# main.net
KiCad netlist of a schematic drawn in Altium Designer
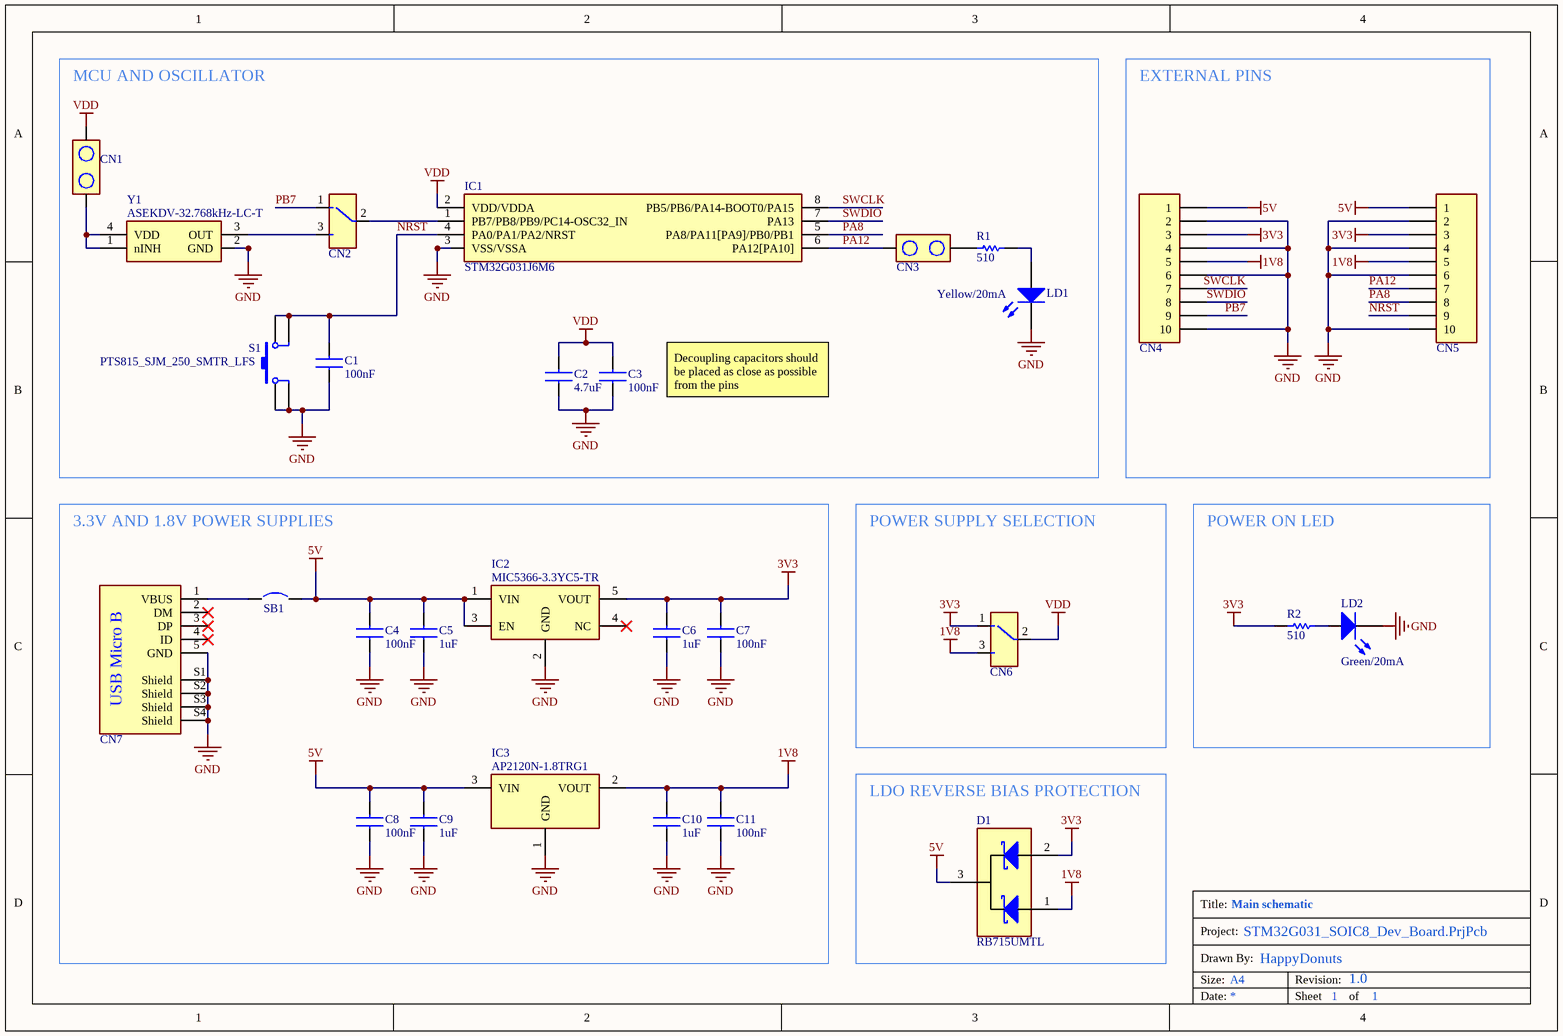
[diagram p0: main.SchDoc]

(export (version "E")
  (design (tool "Eeschema 10.0.6"))
  (components
    (comp (ref "C1")
      (value "100nF")
      (footprint "STM32G031_SOIC8_Dev_Board:CAPC2012X94N")
      (description "Capacitor")
      (fields
        (field (name "MANUFACTURER_PART_NUMBER") "C0805C104K5RAC7411")
        (field (name "MOUSER PART NUMBER") "80-C0805C104K5RACLR")
      )
      (libsource (lib "STM32G031_SOIC8_Dev_Board") (part "C0805C104K5RAC7411"))
    )
    (comp (ref "C2")
      (value "4.7uF")
      (footprint "STM32G031_SOIC8_Dev_Board:CAPC2012X135N")
      (description "Capacitor")
      (fields
        (field (name "MANUFACTURER_PART_NUMBER") "CL21A475KPFNNNE")
        (field (name "MOUSER PART NUMBER") "187-CL21A475KPFNNNE")
      )
      (libsource (lib "STM32G031_SOIC8_Dev_Board") (part "CL21A475KPFNNNE"))
    )
    (comp (ref "C3")
      (value "100nF")
      (footprint "STM32G031_SOIC8_Dev_Board:CAPC2012X94N")
      (description "Capacitor")
      (fields
        (field (name "MANUFACTURER_PART_NUMBER") "C0805C104K5RAC7411")
        (field (name "MOUSER PART NUMBER") "80-C0805C104K5RACLR")
      )
      (libsource (lib "STM32G031_SOIC8_Dev_Board") (part "C0805C104K5RAC7411"))
    )
    (comp (ref "C4")
      (value "100nF")
      (footprint "STM32G031_SOIC8_Dev_Board:CAPC2012X94N")
      (description "Capacitor")
      (fields
        (field (name "MANUFACTURER_PART_NUMBER") "C0805C104K5RAC7411")
        (field (name "MOUSER PART NUMBER") "80-C0805C104K5RACLR")
      )
      (libsource (lib "STM32G031_SOIC8_Dev_Board") (part "C0805C104K5RAC7411"))
    )
    (comp (ref "C5")
      (value "1uF")
      (footprint "STM32G031_SOIC8_Dev_Board:CAPC2012X135N")
      (description "Capacitor")
      (fields
        (field (name "MANUFACTURER_PART_NUMBER") "885012107015")
        (field (name "MOUSER PART NUMBER") "710-885012107015")
      )
      (libsource (lib "STM32G031_SOIC8_Dev_Board") (part "885012107015"))
    )
    (comp (ref "C6")
      (value "1uF")
      (footprint "STM32G031_SOIC8_Dev_Board:CAPC2012X135N")
      (description "Capacitor")
      (fields
        (field (name "MANUFACTURER_PART_NUMBER") "885012107015")
        (field (name "MOUSER PART NUMBER") "710-885012107015")
      )
      (libsource (lib "STM32G031_SOIC8_Dev_Board") (part "885012107015"))
    )
    (comp (ref "C7")
      (value "100nF")
      (footprint "STM32G031_SOIC8_Dev_Board:CAPC2012X94N")
      (description "Capacitor")
      (fields
        (field (name "MANUFACTURER_PART_NUMBER") "C0805C104K5RAC7411")
        (field (name "MOUSER PART NUMBER") "80-C0805C104K5RACLR")
      )
      (libsource (lib "STM32G031_SOIC8_Dev_Board") (part "C0805C104K5RAC7411"))
    )
    (comp (ref "C8")
      (value "100nF")
      (footprint "STM32G031_SOIC8_Dev_Board:CAPC2012X94N")
      (description "Capacitor")
      (fields
        (field (name "MANUFACTURER_PART_NUMBER") "C0805C104K5RAC7411")
        (field (name "MOUSER PART NUMBER") "80-C0805C104K5RACLR")
      )
      (libsource (lib "STM32G031_SOIC8_Dev_Board") (part "C0805C104K5RAC7411"))
    )
    (comp (ref "C9")
      (value "1uF")
      (footprint "STM32G031_SOIC8_Dev_Board:CAPC2012X135N")
      (description "Capacitor")
      (fields
        (field (name "MANUFACTURER_PART_NUMBER") "885012107015")
        (field (name "MOUSER PART NUMBER") "710-885012107015")
      )
      (libsource (lib "STM32G031_SOIC8_Dev_Board") (part "885012107015"))
    )
    (comp (ref "C10")
      (value "1uF")
      (footprint "STM32G031_SOIC8_Dev_Board:CAPC2012X135N")
      (description "Capacitor")
      (fields
        (field (name "MANUFACTURER_PART_NUMBER") "885012107015")
        (field (name "MOUSER PART NUMBER") "710-885012107015")
      )
      (libsource (lib "STM32G031_SOIC8_Dev_Board") (part "885012107015"))
    )
    (comp (ref "C11")
      (value "100nF")
      (footprint "STM32G031_SOIC8_Dev_Board:CAPC2012X94N")
      (description "Capacitor")
      (fields
        (field (name "MANUFACTURER_PART_NUMBER") "C0805C104K5RAC7411")
        (field (name "MOUSER PART NUMBER") "80-C0805C104K5RACLR")
      )
      (libsource (lib "STM32G031_SOIC8_Dev_Board") (part "C0805C104K5RAC7411"))
    )
    (comp (ref "CN1")
      (value "CN_2PIN")
      (footprint "STM32G031_SOIC8_Dev_Board:CN_2PIN")
      (description "Connector")
      (libsource (lib "") (part "CN_2PIN_1"))
    )
    (comp (ref "CN2")
      (value "CN_3PIN")
      (footprint "STM32G031_SOIC8_Dev_Board:CN_3PIN")
      (description "Connector")
      (libsource (lib "STM32G031_SOIC8_Dev_Board") (part "CN_3PIN"))
    )
    (comp (ref "CN3")
      (value "CN_2PIN")
      (footprint "STM32G031_SOIC8_Dev_Board:CN_2PIN")
      (description "Connector")
      (libsource (lib "STM32G031_SOIC8_Dev_Board") (part "CN_2PIN"))
    )
    (comp (ref "CN4")
      (value "CN_10PIN")
      (footprint "STM32G031_SOIC8_Dev_Board:CN_10PIN")
      (description "Connector")
      (libsource (lib "") (part "CN_10PIN_1"))
    )
    (comp (ref "CN5")
      (value "CN_10PIN")
      (footprint "STM32G031_SOIC8_Dev_Board:CN_10PIN")
      (description "Connector")
      (libsource (lib "STM32G031_SOIC8_Dev_Board") (part "CN_10PIN"))
    )
    (comp (ref "CN6")
      (value "CN_3PIN")
      (footprint "STM32G031_SOIC8_Dev_Board:CN_3PIN")
      (description "Connector")
      (libsource (lib "STM32G031_SOIC8_Dev_Board") (part "CN_3PIN"))
    )
    (comp (ref "CN7")
      (value "USB_B_AE")
      (footprint "STM32G031_SOIC8_Dev_Board:USB_B_AE")
      (description "USB connector")
      (libsource (lib "STM32G031_SOIC8_Dev_Board") (part "USB_B_AE"))
    )
    (comp (ref "D1")
      (value "RB715UMTL")
      (footprint "STM32L031_TSSOP20_Dev_Board:DAN217UMTL")
      (description "Schottky Diode")
      (fields (field (name "MOUSER PART NUMBER") "755-RB715UMTL"))
      (libsource (lib "STM32G031_SOIC8_Dev_Board") (part "RB715UMTL"))
    )
    (comp (ref "IC1")
      (value "STM32G031J6M6")
      (footprint "STM32G031_SOIC8_Dev_Board:SOIC127P600X175-8N")
      (description "Integrated Circuit")
      (fields (field (name "MOUSER PART NUMBER") "511-STM32G031J6M6"))
      (libsource (lib "STM32G031_SOIC8_Dev_Board") (part "STM32G031J6M6"))
    )
    (comp (ref "IC2")
      (value "MIC5366-3.3YC5-TR")
      (footprint "STM32G031_SOIC8_Dev_Board:SOT65P210X110-5N")
      (description "LDO")
      (fields
        (field (name "MOUSER PART NUMBER") "998-MIC5366-3.3YC5TR")
        (field (name "ARROW PART NUMBER") "MIC5365-3.3YC5-TR")
      )
      (libsource (lib "STM32G031_SOIC8_Dev_Board") (part "MIC5366-3.3YC5-TR"))
    )
    (comp (ref "IC3")
      (value "AP2120N-1.8TRG1")
      (footprint "STM32G031_SOIC8_Dev_Board:SOT95P230X110-3N")
      (description "LDO")
      (fields (field (name "MOUSER PART NUMBER") "621-AP2120N-1.8TRG1"))
      (libsource (lib "STM32G031_SOIC8_Dev_Board") (part "AP2120N-1.8TRG1"))
    )
    (comp (ref "LD1")
      (value "Yellow/20mA")
      (footprint "STM32G031_SOIC8_Dev_Board:LEDC2012X85N_Y")
      (description "LED")
      (fields
        (field (name "MANUFACTURER_PART_NUMBER") "LTST-C171KSKT")
        (field (name "MOUSER PART NUMBER") "859-LTST-C171KSKT")
      )
      (libsource (lib "STM32G031_SOIC8_Dev_Board") (part "LTST-C171KSKT"))
    )
    (comp (ref "LD2")
      (value "Green/20mA")
      (footprint "STM32G031_SOIC8_Dev_Board:LEDC2012X85N_G")
      (description "LED")
      (fields
        (field (name "MANUFACTURER_PART_NUMBER") "LTST-C171KGKT")
        (field (name "MOUSER PART NUMBER") "859-LTST-C171KGKT")
      )
      (libsource (lib "STM32G031_SOIC8_Dev_Board") (part "LTST-C171KGKT"))
    )
    (comp (ref "R1")
      (value "510")
      (footprint "STM32G031_SOIC8_Dev_Board:RESC2012X60N")
      (description "Resistor")
      (fields
        (field (name "MANUFACTURER_PART_NUMBER") "RC0805FR-07510RL")
        (field (name "MOUSER PART NUMBER") "603-RC0805FR-07510RL")
      )
      (libsource (lib "STM32G031_SOIC8_Dev_Board") (part "RC0805FR-07510RL"))
    )
    (comp (ref "R2")
      (value "510")
      (footprint "STM32G031_SOIC8_Dev_Board:RESC2012X60N")
      (description "Resistor")
      (fields
        (field (name "MANUFACTURER_PART_NUMBER") "RC0805FR-07510RL")
        (field (name "MOUSER PART NUMBER") "603-RC0805FR-07510RL")
      )
      (libsource (lib "STM32G031_SOIC8_Dev_Board") (part "RC0805FR-07510RL"))
    )
    (comp (ref "S1")
      (value "PTS815_SJM_250_SMTR_LFS")
      (footprint "STM32G031_SOIC8_Dev_Board:PTS815SJM250SMTRLFS")
      (description "Switch")
      (fields
        (field (name "MANUFACTURER_PART_NUMBER") "PTS815 SJM 250 SMTR LFS")
        (field (name "MOUSER PART NUMBER") "611-PTS815SJM250SMTR")
      )
      (libsource (lib "STM32G031_SOIC8_Dev_Board") (part "PTS815_SJM_250_SMTR_LFS"))
    )
    (comp (ref "SB1")
      (value "RC0805FR-070RL")
      (footprint "STM32G031_SOIC8_Dev_Board:RESC2012X60N")
      (description "Jumper (0 ohm)")
      (fields (field (name "MOUSER PART NUMBER") "603-RC0805FR-070RL"))
      (libsource (lib "STM32G031_SOIC8_Dev_Board") (part "RC0805FR-070RL"))
    )
    (comp (ref "Y1")
      (value "ASEKDV-32.768kHz-LC-T")
      (footprint "STM32G031_SOIC8_Dev_Board:ASEKDV-32.768kHz-LC-T")
      (description "Crystal or Oscillator")
      (fields (field (name "MOUSER PART NUMBER") "815-ASEKDV32768KHLCT"))
      (libsource (lib "STM32G031_SOIC8_Dev_Board") (part "ASEKDV-32.768kHz-LC-T"))
    )
  )
  (nets
    (net (code "1") (name "/NRST") (class "Default")
      (node (ref "C1") (pin "2") (pinfunction "2_2") (pintype "passive"))
      (node (ref "CN5") (pin "9") (pinfunction "9_9") (pintype "passive"))
      (node (ref "IC1") (pin "4") (pinfunction "PA0/PA1/PA2/NRST_4") (pintype "passive"))
      (node (ref "S1") (pin "3") (pinfunction "3_3") (pintype "passive"))
      (node (ref "S1") (pin "4") (pinfunction "4_4") (pintype "passive"))
    )
    (net (code "2") (name "/PA8") (class "Default")
      (node (ref "CN5") (pin "8") (pinfunction "8_8") (pintype "passive"))
      (node (ref "IC1") (pin "5") (pinfunction "PA8/PA11[PA9]/PB0/PB1_5") (pintype "passive"))
    )
    (net (code "3") (name "/PA12") (class "Default")
      (node (ref "CN3") (pin "1") (pinfunction "1_1") (pintype "passive"))
      (node (ref "CN5") (pin "7") (pinfunction "7_7") (pintype "passive"))
      (node (ref "IC1") (pin "6") (pinfunction "PA12[PA10]_6") (pintype "passive"))
    )
    (net (code "4") (name "/PB7") (class "Default")
      (node (ref "CN2") (pin "1") (pinfunction "1_1") (pintype "passive"))
      (node (ref "CN4") (pin "9") (pinfunction "9_9") (pintype "passive"))
    )
    (net (code "5") (name "/SWCLK") (class "Default")
      (node (ref "CN4") (pin "7") (pinfunction "7_7") (pintype "passive"))
      (node (ref "IC1") (pin "8") (pinfunction "PB5/PB6/PA14-BOOT0/PA15_8") (pintype "passive"))
    )
    (net (code "6") (name "/SWDIO") (class "Default")
      (node (ref "CN4") (pin "8") (pinfunction "8_8") (pintype "passive"))
      (node (ref "IC1") (pin "7") (pinfunction "PA13_7") (pintype "passive"))
    )
    (net (code "7") (name "1V8") (class "Default")
      (node (ref "C10") (pin "2") (pinfunction "2_2") (pintype "passive"))
      (node (ref "C11") (pin "2") (pinfunction "2_2") (pintype "passive"))
      (node (ref "CN4") (pin "5") (pinfunction "5_5") (pintype "passive"))
      (node (ref "CN5") (pin "5") (pinfunction "5_5") (pintype "passive"))
      (node (ref "CN6") (pin "3") (pinfunction "3_3") (pintype "passive"))
      (node (ref "D1") (pin "1") (pinfunction "K_1_1") (pintype "passive"))
      (node (ref "IC3") (pin "2") (pinfunction "VOUT_2") (pintype "passive"))
    )
    (net (code "8") (name "3V3") (class "Default")
      (node (ref "C6") (pin "2") (pinfunction "2_2") (pintype "passive"))
      (node (ref "C7") (pin "2") (pinfunction "2_2") (pintype "passive"))
      (node (ref "CN4") (pin "3") (pinfunction "3_3") (pintype "passive"))
      (node (ref "CN5") (pin "3") (pinfunction "3_3") (pintype "passive"))
      (node (ref "CN6") (pin "1") (pinfunction "1_1") (pintype "passive"))
      (node (ref "D1") (pin "2") (pinfunction "K_2_2") (pintype "passive"))
      (node (ref "IC2") (pin "5") (pinfunction "VOUT_5") (pintype "passive"))
      (node (ref "R2") (pin "1") (pinfunction "1_1") (pintype "passive"))
    )
    (net (code "9") (name "5V") (class "Default")
      (node (ref "C4") (pin "2") (pinfunction "2_2") (pintype "passive"))
      (node (ref "C5") (pin "2") (pinfunction "2_2") (pintype "passive"))
      (node (ref "C8") (pin "2") (pinfunction "2_2") (pintype "passive"))
      (node (ref "C9") (pin "2") (pinfunction "2_2") (pintype "passive"))
      (node (ref "CN4") (pin "1") (pinfunction "1_1") (pintype "passive"))
      (node (ref "CN5") (pin "1") (pinfunction "1_1") (pintype "passive"))
      (node (ref "D1") (pin "3") (pinfunction "COM_A_3") (pintype "passive"))
      (node (ref "IC2") (pin "1") (pinfunction "VIN_1") (pintype "power_in"))
      (node (ref "IC2") (pin "3") (pinfunction "EN_3") (pintype "passive"))
      (node (ref "IC3") (pin "3") (pinfunction "VIN_3") (pintype "passive"))
      (node (ref "SB1") (pin "2") (pinfunction "2_2") (pintype "passive"))
    )
    (net (code "10") (name "GND") (class "Default")
      (node (ref "C1") (pin "1") (pinfunction "1_1") (pintype "passive"))
      (node (ref "C10") (pin "1") (pinfunction "1_1") (pintype "passive"))
      (node (ref "C11") (pin "1") (pinfunction "1_1") (pintype "passive"))
      (node (ref "C2") (pin "1") (pinfunction "1_1") (pintype "passive"))
      (node (ref "C3") (pin "1") (pinfunction "1_1") (pintype "passive"))
      (node (ref "C4") (pin "1") (pinfunction "1_1") (pintype "passive"))
      (node (ref "C5") (pin "1") (pinfunction "1_1") (pintype "passive"))
      (node (ref "C6") (pin "1") (pinfunction "1_1") (pintype "passive"))
      (node (ref "C7") (pin "1") (pinfunction "1_1") (pintype "passive"))
      (node (ref "C8") (pin "1") (pinfunction "1_1") (pintype "passive"))
      (node (ref "C9") (pin "1") (pinfunction "1_1") (pintype "passive"))
      (node (ref "CN4") (pin "10") (pinfunction "10_10") (pintype "passive"))
      (node (ref "CN4") (pin "2") (pinfunction "2_2") (pintype "passive"))
      (node (ref "CN4") (pin "4") (pinfunction "4_4") (pintype "passive"))
      (node (ref "CN4") (pin "6") (pinfunction "6_6") (pintype "passive"))
      (node (ref "CN5") (pin "10") (pinfunction "10_10") (pintype "passive"))
      (node (ref "CN5") (pin "2") (pinfunction "2_2") (pintype "passive"))
      (node (ref "CN5") (pin "4") (pinfunction "4_4") (pintype "passive"))
      (node (ref "CN5") (pin "6") (pinfunction "6_6") (pintype "passive"))
      (node (ref "CN7") (pin "5") (pinfunction "GND_5") (pintype "passive"))
      (node (ref "CN7") (pin "S1") (pinfunction "Shield_S1") (pintype "passive"))
      (node (ref "CN7") (pin "S2") (pinfunction "Shield_S2") (pintype "passive"))
      (node (ref "CN7") (pin "S3") (pinfunction "Shield_S3") (pintype "passive"))
      (node (ref "CN7") (pin "S4") (pinfunction "Shield_S4") (pintype "passive"))
      (node (ref "IC1") (pin "3") (pinfunction "VSS/VSSA_3") (pintype "passive"))
      (node (ref "IC2") (pin "2") (pinfunction "GND_2") (pintype "power_in"))
      (node (ref "IC3") (pin "1") (pinfunction "GND_1") (pintype "power_in"))
      (node (ref "LD1") (pin "1") (pinfunction "K_1") (pintype "passive"))
      (node (ref "LD2") (pin "1") (pinfunction "K_1") (pintype "passive"))
      (node (ref "S1") (pin "1") (pinfunction "1_1") (pintype "passive"))
      (node (ref "S1") (pin "2") (pinfunction "2_2") (pintype "passive"))
      (node (ref "Y1") (pin "2") (pinfunction "GND_2") (pintype "passive"))
    )
    (net (code "11") (name "Net-(CN3-Pad2)") (class "Default")
      (node (ref "CN3") (pin "2") (pinfunction "2_2") (pintype "passive"))
      (node (ref "R1") (pin "1") (pinfunction "1_1") (pintype "passive"))
    )
    (net (code "12") (name "Net-(CN7-VBUS)") (class "Default")
      (node (ref "CN7") (pin "1") (pinfunction "VBUS_1") (pintype "passive"))
      (node (ref "SB1") (pin "1") (pinfunction "1_1") (pintype "passive"))
    )
    (net (code "13") (name "Net-(IC1-PB7{slash}PB8{slash}PB9{slash}PC14-OSC32_IN)") (class "Default")
      (node (ref "CN2") (pin "2") (pinfunction "2_2") (pintype "passive"))
      (node (ref "IC1") (pin "1") (pinfunction "PB7/PB8/PB9/PC14-OSC32_IN_1") (pintype "passive"))
    )
    (net (code "14") (name "Net-(LD1-A)") (class "Default")
      (node (ref "LD1") (pin "2") (pinfunction "A_2") (pintype "passive"))
      (node (ref "R1") (pin "2") (pinfunction "2_2") (pintype "passive"))
    )
    (net (code "15") (name "Net-(LD2-A)") (class "Default")
      (node (ref "LD2") (pin "2") (pinfunction "A_2") (pintype "passive"))
      (node (ref "R2") (pin "2") (pinfunction "2_2") (pintype "passive"))
    )
    (net (code "16") (name "Net-(Y1-OUT)") (class "Default")
      (node (ref "CN2") (pin "3") (pinfunction "3_3") (pintype "passive"))
      (node (ref "Y1") (pin "3") (pinfunction "OUT_3") (pintype "passive"))
    )
    (net (code "17") (name "Net-(Y1-VDD)") (class "Default")
      (node (ref "CN1") (pin "1") (pinfunction "1_1") (pintype "passive"))
      (node (ref "Y1") (pin "1") (pinfunction "nINH_1") (pintype "passive"))
      (node (ref "Y1") (pin "4") (pinfunction "VDD_4") (pintype "passive"))
    )
    (net (code "18") (name "VDD") (class "Default")
      (node (ref "C2") (pin "2") (pinfunction "2_2") (pintype "passive"))
      (node (ref "C3") (pin "2") (pinfunction "2_2") (pintype "passive"))
      (node (ref "CN1") (pin "2") (pinfunction "2_2") (pintype "passive"))
      (node (ref "CN6") (pin "2") (pinfunction "2_2") (pintype "passive"))
      (node (ref "IC1") (pin "2") (pinfunction "VDD/VDDA_2") (pintype "passive"))
    )
    (net (code "19") (name "unconnected-(CN7-DM-Pad2)") (class "Default")
      (node (ref "CN7") (pin "2") (pinfunction "DM_2") (pintype "passive+no_connect"))
    )
    (net (code "20") (name "unconnected-(CN7-DP-Pad3)") (class "Default")
      (node (ref "CN7") (pin "3") (pinfunction "DP_3") (pintype "passive+no_connect"))
    )
    (net (code "21") (name "unconnected-(CN7-ID-Pad4)") (class "Default")
      (node (ref "CN7") (pin "4") (pinfunction "ID_4") (pintype "passive+no_connect"))
    )
    (net (code "22") (name "unconnected-(IC2-NC-Pad4)") (class "Default")
      (node (ref "IC2") (pin "4") (pinfunction "NC_4") (pintype "passive+no_connect"))
    )
  )
)
